# ido.net
KiCad netlist of a schematic drawn in EAGLE
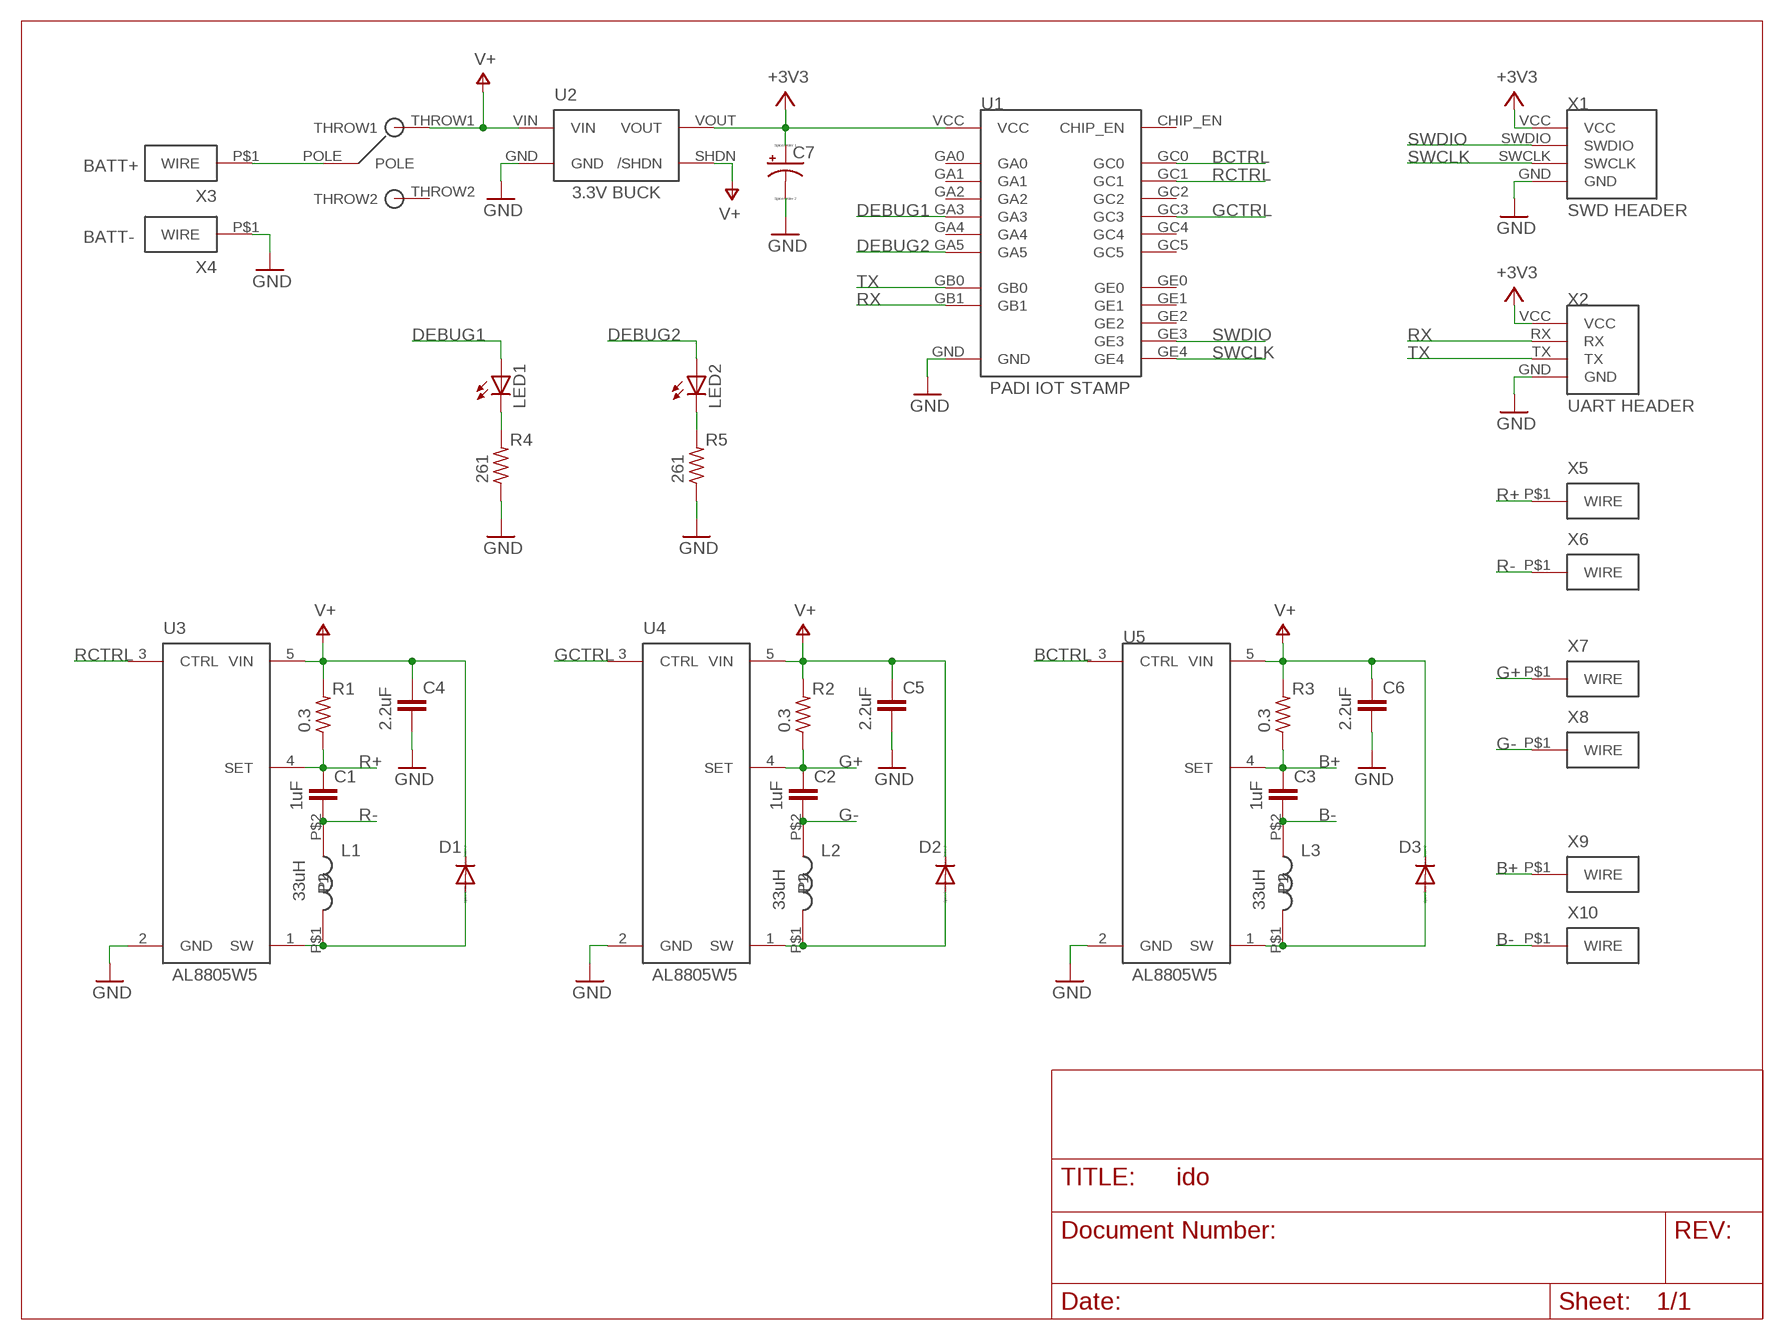
[diagram p0: schematic, sheet 1]

(export (version "E")
  (design (tool "Eeschema 10.0.6"))
  (components
    (comp (ref "C1")
      (value "1uF")
      (footprint "eagle-import:C0603")
      (libsource (lib "eagle-import") (part "C-EUC0603"))
    )
    (comp (ref "C2")
      (value "1uF")
      (footprint "eagle-import:C0603")
      (libsource (lib "eagle-import") (part "C-EUC0603"))
    )
    (comp (ref "C3")
      (value "1uF")
      (footprint "eagle-import:C0603")
      (libsource (lib "eagle-import") (part "C-EUC0603"))
    )
    (comp (ref "C4")
      (value "2.2uF")
      (footprint "eagle-import:C0603")
      (libsource (lib "eagle-import") (part "C-EUC0603"))
    )
    (comp (ref "C5")
      (value "2.2uF")
      (footprint "eagle-import:C0603")
      (libsource (lib "eagle-import") (part "C-EUC0603"))
    )
    (comp (ref "C6")
      (value "2.2uF")
      (footprint "eagle-import:C0603")
      (libsource (lib "eagle-import") (part "C-EUC0603"))
    )
    (comp (ref "C7")
      (value "CPOL-USE2.5-7")
      (footprint "eagle-import:E2,5-7")
      (libsource (lib "eagle-import") (part "CPOL-USE2.5-7"))
    )
    (comp (ref "D1")
      (value "DIODE-DO214AC")
      (footprint "eagle-import:DO214AC")
      (libsource (lib "eagle-import") (part "DIODE-DO214AC"))
    )
    (comp (ref "D2")
      (value "DIODE-DO214AC")
      (footprint "eagle-import:DO214AC")
      (libsource (lib "eagle-import") (part "DIODE-DO214AC"))
    )
    (comp (ref "D3")
      (value "DIODE-DO214AC")
      (footprint "eagle-import:DO214AC")
      (libsource (lib "eagle-import") (part "DIODE-DO214AC"))
    )
    (comp (ref "L1")
      (value "33uH")
      (footprint "eagle-import:MURATA-INDUCTOR")
      (libsource (lib "eagle-import") (part "MURATA-INDUCTOR"))
    )
    (comp (ref "L2")
      (value "33uH")
      (footprint "eagle-import:MURATA-INDUCTOR")
      (libsource (lib "eagle-import") (part "MURATA-INDUCTOR"))
    )
    (comp (ref "L3")
      (value "33uH")
      (footprint "eagle-import:MURATA-INDUCTOR")
      (libsource (lib "eagle-import") (part "MURATA-INDUCTOR"))
    )
    (comp (ref "LED1")
      (value "LEDCHIPLED_0603")
      (footprint "eagle-import:CHIPLED_0603")
      (libsource (lib "eagle-import") (part "LEDCHIPLED_0603"))
    )
    (comp (ref "LED2")
      (value "LEDCHIPLED_0603")
      (footprint "eagle-import:CHIPLED_0603")
      (libsource (lib "eagle-import") (part "LEDCHIPLED_0603"))
    )
    (comp (ref "R1")
      (value "0.3")
      (footprint "eagle-import:R0603")
      (libsource (lib "eagle-import") (part "R-US_R0603"))
    )
    (comp (ref "R2")
      (value "0.3")
      (footprint "eagle-import:R0603")
      (libsource (lib "eagle-import") (part "R-US_R0603"))
    )
    (comp (ref "R3")
      (value "0.3")
      (footprint "eagle-import:R0603")
      (libsource (lib "eagle-import") (part "R-US_R0603"))
    )
    (comp (ref "R4")
      (value "261")
      (footprint "eagle-import:R0603")
      (libsource (lib "eagle-import") (part "R-US_R0603"))
    )
    (comp (ref "R5")
      (value "261")
      (footprint "eagle-import:R0603")
      (libsource (lib "eagle-import") (part "R-US_R0603"))
    )
    (comp (ref "S1")
      (value "SLIDE-SWITCH")
      (footprint "eagle-import:SLIDE-SWITCH")
      (libsource (lib "eagle-import") (part "SLIDE-SWITCH"))
    )
    (comp (ref "U1")
      (value "PADI-IOT-STAMP")
      (footprint "eagle-import:PADI-IOT-STAMP")
      (libsource (lib "eagle-import") (part "PADI-IOT-STAMP"))
    )
    (comp (ref "U2")
      (value "POLOLU-BUCK")
      (footprint "eagle-import:POLOLU-BUCK")
      (libsource (lib "eagle-import") (part "POLOLU-BUCK"))
    )
    (comp (ref "U3")
      (value "AL8805W5")
      (footprint "eagle-import:SOT25")
      (libsource (lib "eagle-import") (part "AL8805W5"))
    )
    (comp (ref "U4")
      (value "AL8805W5")
      (footprint "eagle-import:SOT25")
      (libsource (lib "eagle-import") (part "AL8805W5"))
    )
    (comp (ref "U5")
      (value "AL8805W5")
      (footprint "eagle-import:SOT25")
      (libsource (lib "eagle-import") (part "AL8805W5"))
    )
    (comp (ref "X1")
      (value "PROGRAMMING-HEADER")
      (footprint "eagle-import:PROGRAMMING-HEADER")
      (libsource (lib "eagle-import") (part "PROGRAMMING-HEADER"))
    )
    (comp (ref "X2")
      (value "UART-HEADER")
      (footprint "eagle-import:UART-HEADER")
      (libsource (lib "eagle-import") (part "UART-HEADER"))
    )
    (comp (ref "X3")
      (value "WIRE-HOLE")
      (footprint "eagle-import:WIRE-HOLE")
      (libsource (lib "eagle-import") (part "WIRE-HOLE"))
    )
    (comp (ref "X4")
      (value "WIRE-HOLE")
      (footprint "eagle-import:WIRE-HOLE")
      (libsource (lib "eagle-import") (part "WIRE-HOLE"))
    )
    (comp (ref "X5")
      (value "WIRE-HOLE")
      (footprint "eagle-import:WIRE-HOLE")
      (libsource (lib "eagle-import") (part "WIRE-HOLE"))
    )
    (comp (ref "X6")
      (value "WIRE-HOLE")
      (footprint "eagle-import:WIRE-HOLE")
      (libsource (lib "eagle-import") (part "WIRE-HOLE"))
    )
    (comp (ref "X7")
      (value "WIRE-HOLE")
      (footprint "eagle-import:WIRE-HOLE")
      (libsource (lib "eagle-import") (part "WIRE-HOLE"))
    )
    (comp (ref "X8")
      (value "WIRE-HOLE")
      (footprint "eagle-import:WIRE-HOLE")
      (libsource (lib "eagle-import") (part "WIRE-HOLE"))
    )
    (comp (ref "X9")
      (value "WIRE-HOLE")
      (footprint "eagle-import:WIRE-HOLE")
      (libsource (lib "eagle-import") (part "WIRE-HOLE"))
    )
    (comp (ref "X10")
      (value "WIRE-HOLE")
      (footprint "eagle-import:WIRE-HOLE")
      (libsource (lib "eagle-import") (part "WIRE-HOLE"))
    )
  )
  (nets
    (net (code "1") (name "+3V3") (class "Default")
      (node (ref "C7") (pin "+") (pinfunction "+_+") (pintype "passive"))
      (node (ref "U1") (pin "VCC") (pinfunction "VCC_VCC") (pintype "bidirectional"))
      (node (ref "U2") (pin "VOUT") (pinfunction "VOUT_VOUT") (pintype "bidirectional"))
      (node (ref "X1") (pin "VCC") (pinfunction "VCC_VCC") (pintype "bidirectional"))
      (node (ref "X2") (pin "VCC") (pinfunction "VCC_VCC") (pintype "bidirectional"))
    )
    (net (code "2") (name "/B+") (class "Default")
      (node (ref "C3") (pin "1") (pinfunction "1_1") (pintype "passive"))
      (node (ref "R3") (pin "1") (pinfunction "1_1") (pintype "passive"))
      (node (ref "U5") (pin "4") (pinfunction "SET_4") (pintype "bidirectional"))
      (node (ref "X9") (pin "P$1") (pinfunction "WIRE_P$1") (pintype "bidirectional"))
    )
    (net (code "3") (name "/B-") (class "Default")
      (node (ref "C3") (pin "2") (pinfunction "2_2") (pintype "passive"))
      (node (ref "L3") (pin "P$2") (pinfunction "P2_P$2") (pintype "bidirectional"))
      (node (ref "X10") (pin "P$1") (pinfunction "WIRE_P$1") (pintype "bidirectional"))
    )
    (net (code "4") (name "/BCTRL") (class "Default")
      (node (ref "U1") (pin "GC0") (pinfunction "GC0_GC0") (pintype "bidirectional"))
      (node (ref "U5") (pin "3") (pinfunction "CTRL_3") (pintype "bidirectional"))
    )
    (net (code "5") (name "/DEBUG1") (class "Default")
      (node (ref "LED1") (pin "A") (pinfunction "A_A") (pintype "passive"))
      (node (ref "U1") (pin "GA3") (pinfunction "GA3_GA3") (pintype "bidirectional"))
    )
    (net (code "6") (name "/DEBUG2") (class "Default")
      (node (ref "LED2") (pin "A") (pinfunction "A_A") (pintype "passive"))
      (node (ref "U1") (pin "GA5") (pinfunction "GA5_GA5") (pintype "bidirectional"))
    )
    (net (code "7") (name "/G+") (class "Default")
      (node (ref "C2") (pin "1") (pinfunction "1_1") (pintype "passive"))
      (node (ref "R2") (pin "1") (pinfunction "1_1") (pintype "passive"))
      (node (ref "U4") (pin "4") (pinfunction "SET_4") (pintype "bidirectional"))
      (node (ref "X7") (pin "P$1") (pinfunction "WIRE_P$1") (pintype "bidirectional"))
    )
    (net (code "8") (name "/G-") (class "Default")
      (node (ref "C2") (pin "2") (pinfunction "2_2") (pintype "passive"))
      (node (ref "L2") (pin "P$2") (pinfunction "P2_P$2") (pintype "bidirectional"))
      (node (ref "X8") (pin "P$1") (pinfunction "WIRE_P$1") (pintype "bidirectional"))
    )
    (net (code "9") (name "/GCTRL") (class "Default")
      (node (ref "U1") (pin "GC3") (pinfunction "GC3_GC3") (pintype "bidirectional"))
      (node (ref "U4") (pin "3") (pinfunction "CTRL_3") (pintype "bidirectional"))
    )
    (net (code "10") (name "/R+") (class "Default")
      (node (ref "C1") (pin "1") (pinfunction "1_1") (pintype "passive"))
      (node (ref "R1") (pin "1") (pinfunction "1_1") (pintype "passive"))
      (node (ref "U3") (pin "4") (pinfunction "SET_4") (pintype "bidirectional"))
      (node (ref "X5") (pin "P$1") (pinfunction "WIRE_P$1") (pintype "bidirectional"))
    )
    (net (code "11") (name "/R-") (class "Default")
      (node (ref "C1") (pin "2") (pinfunction "2_2") (pintype "passive"))
      (node (ref "L1") (pin "P$2") (pinfunction "P2_P$2") (pintype "bidirectional"))
      (node (ref "X6") (pin "P$1") (pinfunction "WIRE_P$1") (pintype "bidirectional"))
    )
    (net (code "12") (name "/RCTRL") (class "Default")
      (node (ref "U1") (pin "GC1") (pinfunction "GC1_GC1") (pintype "bidirectional"))
      (node (ref "U3") (pin "3") (pinfunction "CTRL_3") (pintype "bidirectional"))
    )
    (net (code "13") (name "/RX") (class "Default")
      (node (ref "U1") (pin "GB1") (pinfunction "GB1_GB1") (pintype "bidirectional"))
      (node (ref "X2") (pin "RX") (pinfunction "RX_RX") (pintype "bidirectional"))
    )
    (net (code "14") (name "/SWCLK") (class "Default")
      (node (ref "U1") (pin "GE4") (pinfunction "GE4_GE4") (pintype "bidirectional"))
      (node (ref "X1") (pin "SWCLK") (pinfunction "SWCLK_SWCLK") (pintype "bidirectional"))
    )
    (net (code "15") (name "/SWDIO") (class "Default")
      (node (ref "U1") (pin "GE3") (pinfunction "GE3_GE3") (pintype "bidirectional"))
      (node (ref "X1") (pin "SWDIO") (pinfunction "SWDIO_SWDIO") (pintype "bidirectional"))
    )
    (net (code "16") (name "/TX") (class "Default")
      (node (ref "U1") (pin "GB0") (pinfunction "GB0_GB0") (pintype "bidirectional"))
      (node (ref "X2") (pin "TX") (pinfunction "TX_TX") (pintype "bidirectional"))
    )
    (net (code "17") (name "GND") (class "Default")
      (node (ref "C4") (pin "2") (pinfunction "2_2") (pintype "passive"))
      (node (ref "C5") (pin "2") (pinfunction "2_2") (pintype "passive"))
      (node (ref "C6") (pin "2") (pinfunction "2_2") (pintype "passive"))
      (node (ref "C7") (pin "-") (pinfunction "-_-") (pintype "passive"))
      (node (ref "R4") (pin "1") (pinfunction "1_1") (pintype "passive"))
      (node (ref "R5") (pin "1") (pinfunction "1_1") (pintype "passive"))
      (node (ref "U1") (pin "GND") (pinfunction "GND_GND") (pintype "bidirectional"))
      (node (ref "U2") (pin "GND") (pinfunction "GND_GND") (pintype "bidirectional"))
      (node (ref "U3") (pin "2") (pinfunction "GND_2") (pintype "bidirectional"))
      (node (ref "U4") (pin "2") (pinfunction "GND_2") (pintype "bidirectional"))
      (node (ref "U5") (pin "2") (pinfunction "GND_2") (pintype "bidirectional"))
      (node (ref "X1") (pin "GND") (pinfunction "GND_GND") (pintype "bidirectional"))
      (node (ref "X2") (pin "GND") (pinfunction "GND_GND") (pintype "bidirectional"))
      (node (ref "X4") (pin "P$1") (pinfunction "WIRE_P$1") (pintype "bidirectional"))
    )
    (net (code "18") (name "Net-(L1-P1)") (class "Default")
      (node (ref "D1") (pin "A") (pinfunction "A_A") (pintype "passive"))
      (node (ref "L1") (pin "P$1") (pinfunction "P1_P$1") (pintype "bidirectional"))
      (node (ref "U3") (pin "1") (pinfunction "SW_1") (pintype "bidirectional"))
    )
    (net (code "19") (name "Net-(L2-P1)") (class "Default")
      (node (ref "D2") (pin "A") (pinfunction "A_A") (pintype "passive"))
      (node (ref "L2") (pin "P$1") (pinfunction "P1_P$1") (pintype "bidirectional"))
      (node (ref "U4") (pin "1") (pinfunction "SW_1") (pintype "bidirectional"))
    )
    (net (code "20") (name "Net-(L3-P1)") (class "Default")
      (node (ref "D3") (pin "A") (pinfunction "A_A") (pintype "passive"))
      (node (ref "L3") (pin "P$1") (pinfunction "P1_P$1") (pintype "bidirectional"))
      (node (ref "U5") (pin "1") (pinfunction "SW_1") (pintype "bidirectional"))
    )
    (net (code "21") (name "Net-(LED1-PadC)") (class "Default")
      (node (ref "LED1") (pin "C") (pinfunction "C_C") (pintype "passive"))
      (node (ref "R4") (pin "2") (pinfunction "2_2") (pintype "passive"))
    )
    (net (code "22") (name "Net-(LED2-PadC)") (class "Default")
      (node (ref "LED2") (pin "C") (pinfunction "C_C") (pintype "passive"))
      (node (ref "R5") (pin "2") (pinfunction "2_2") (pintype "passive"))
    )
    (net (code "23") (name "Net-(X3-WIRE)") (class "Default")
      (node (ref "S1") (pin "POLE") (pinfunction "POLE_POLE") (pintype "bidirectional"))
      (node (ref "X3") (pin "P$1") (pinfunction "WIRE_P$1") (pintype "bidirectional"))
    )
    (net (code "24") (name "V+") (class "Default")
      (node (ref "C4") (pin "1") (pinfunction "1_1") (pintype "passive"))
      (node (ref "C5") (pin "1") (pinfunction "1_1") (pintype "passive"))
      (node (ref "C6") (pin "1") (pinfunction "1_1") (pintype "passive"))
      (node (ref "D1") (pin "C") (pinfunction "C_C") (pintype "passive"))
      (node (ref "D2") (pin "C") (pinfunction "C_C") (pintype "passive"))
      (node (ref "D3") (pin "C") (pinfunction "C_C") (pintype "passive"))
      (node (ref "R1") (pin "2") (pinfunction "2_2") (pintype "passive"))
      (node (ref "R2") (pin "2") (pinfunction "2_2") (pintype "passive"))
      (node (ref "R3") (pin "2") (pinfunction "2_2") (pintype "passive"))
      (node (ref "S1") (pin "THROW1") (pinfunction "THROW1_THROW1") (pintype "bidirectional"))
      (node (ref "U2") (pin "SHDN") (pinfunction "/SHDN_SHDN") (pintype "bidirectional"))
      (node (ref "U2") (pin "VIN") (pinfunction "VIN_VIN") (pintype "bidirectional"))
      (node (ref "U3") (pin "5") (pinfunction "VIN_5") (pintype "bidirectional"))
      (node (ref "U4") (pin "5") (pinfunction "VIN_5") (pintype "bidirectional"))
      (node (ref "U5") (pin "5") (pinfunction "VIN_5") (pintype "bidirectional"))
    )
    (net (code "25") (name "unconnected-(S1-PadTHROW2)") (class "Default")
      (node (ref "S1") (pin "THROW2") (pinfunction "THROW2_THROW2") (pintype "bidirectional"))
    )
    (net (code "26") (name "unconnected-(U1-PadCHIP_EN)") (class "Default")
      (node (ref "U1") (pin "CHIP_EN") (pinfunction "CHIP_EN_CHIP_EN") (pintype "bidirectional"))
    )
    (net (code "27") (name "unconnected-(U1-PadGA0)") (class "Default")
      (node (ref "U1") (pin "GA0") (pinfunction "GA0_GA0") (pintype "bidirectional"))
    )
    (net (code "28") (name "unconnected-(U1-PadGA1)") (class "Default")
      (node (ref "U1") (pin "GA1") (pinfunction "GA1_GA1") (pintype "bidirectional"))
    )
    (net (code "29") (name "unconnected-(U1-PadGA2)") (class "Default")
      (node (ref "U1") (pin "GA2") (pinfunction "GA2_GA2") (pintype "bidirectional"))
    )
    (net (code "30") (name "unconnected-(U1-PadGA4)") (class "Default")
      (node (ref "U1") (pin "GA4") (pinfunction "GA4_GA4") (pintype "bidirectional"))
    )
    (net (code "31") (name "unconnected-(U1-PadGC2)") (class "Default")
      (node (ref "U1") (pin "GC2") (pinfunction "GC2_GC2") (pintype "bidirectional"))
    )
    (net (code "32") (name "unconnected-(U1-PadGC4)") (class "Default")
      (node (ref "U1") (pin "GC4") (pinfunction "GC4_GC4") (pintype "bidirectional"))
    )
    (net (code "33") (name "unconnected-(U1-PadGC5)") (class "Default")
      (node (ref "U1") (pin "GC5") (pinfunction "GC5_GC5") (pintype "bidirectional"))
    )
    (net (code "34") (name "unconnected-(U1-PadGE0)") (class "Default")
      (node (ref "U1") (pin "GE0") (pinfunction "GE0_GE0") (pintype "bidirectional"))
    )
    (net (code "35") (name "unconnected-(U1-PadGE1)") (class "Default")
      (node (ref "U1") (pin "GE1") (pinfunction "GE1_GE1") (pintype "bidirectional"))
    )
    (net (code "36") (name "unconnected-(U1-PadGE2)") (class "Default")
      (node (ref "U1") (pin "GE2") (pinfunction "GE2_GE2") (pintype "bidirectional"))
    )
  )
)
